# contactor_feedback.net
KiCad netlist of a schematic drawn in Altium Designer
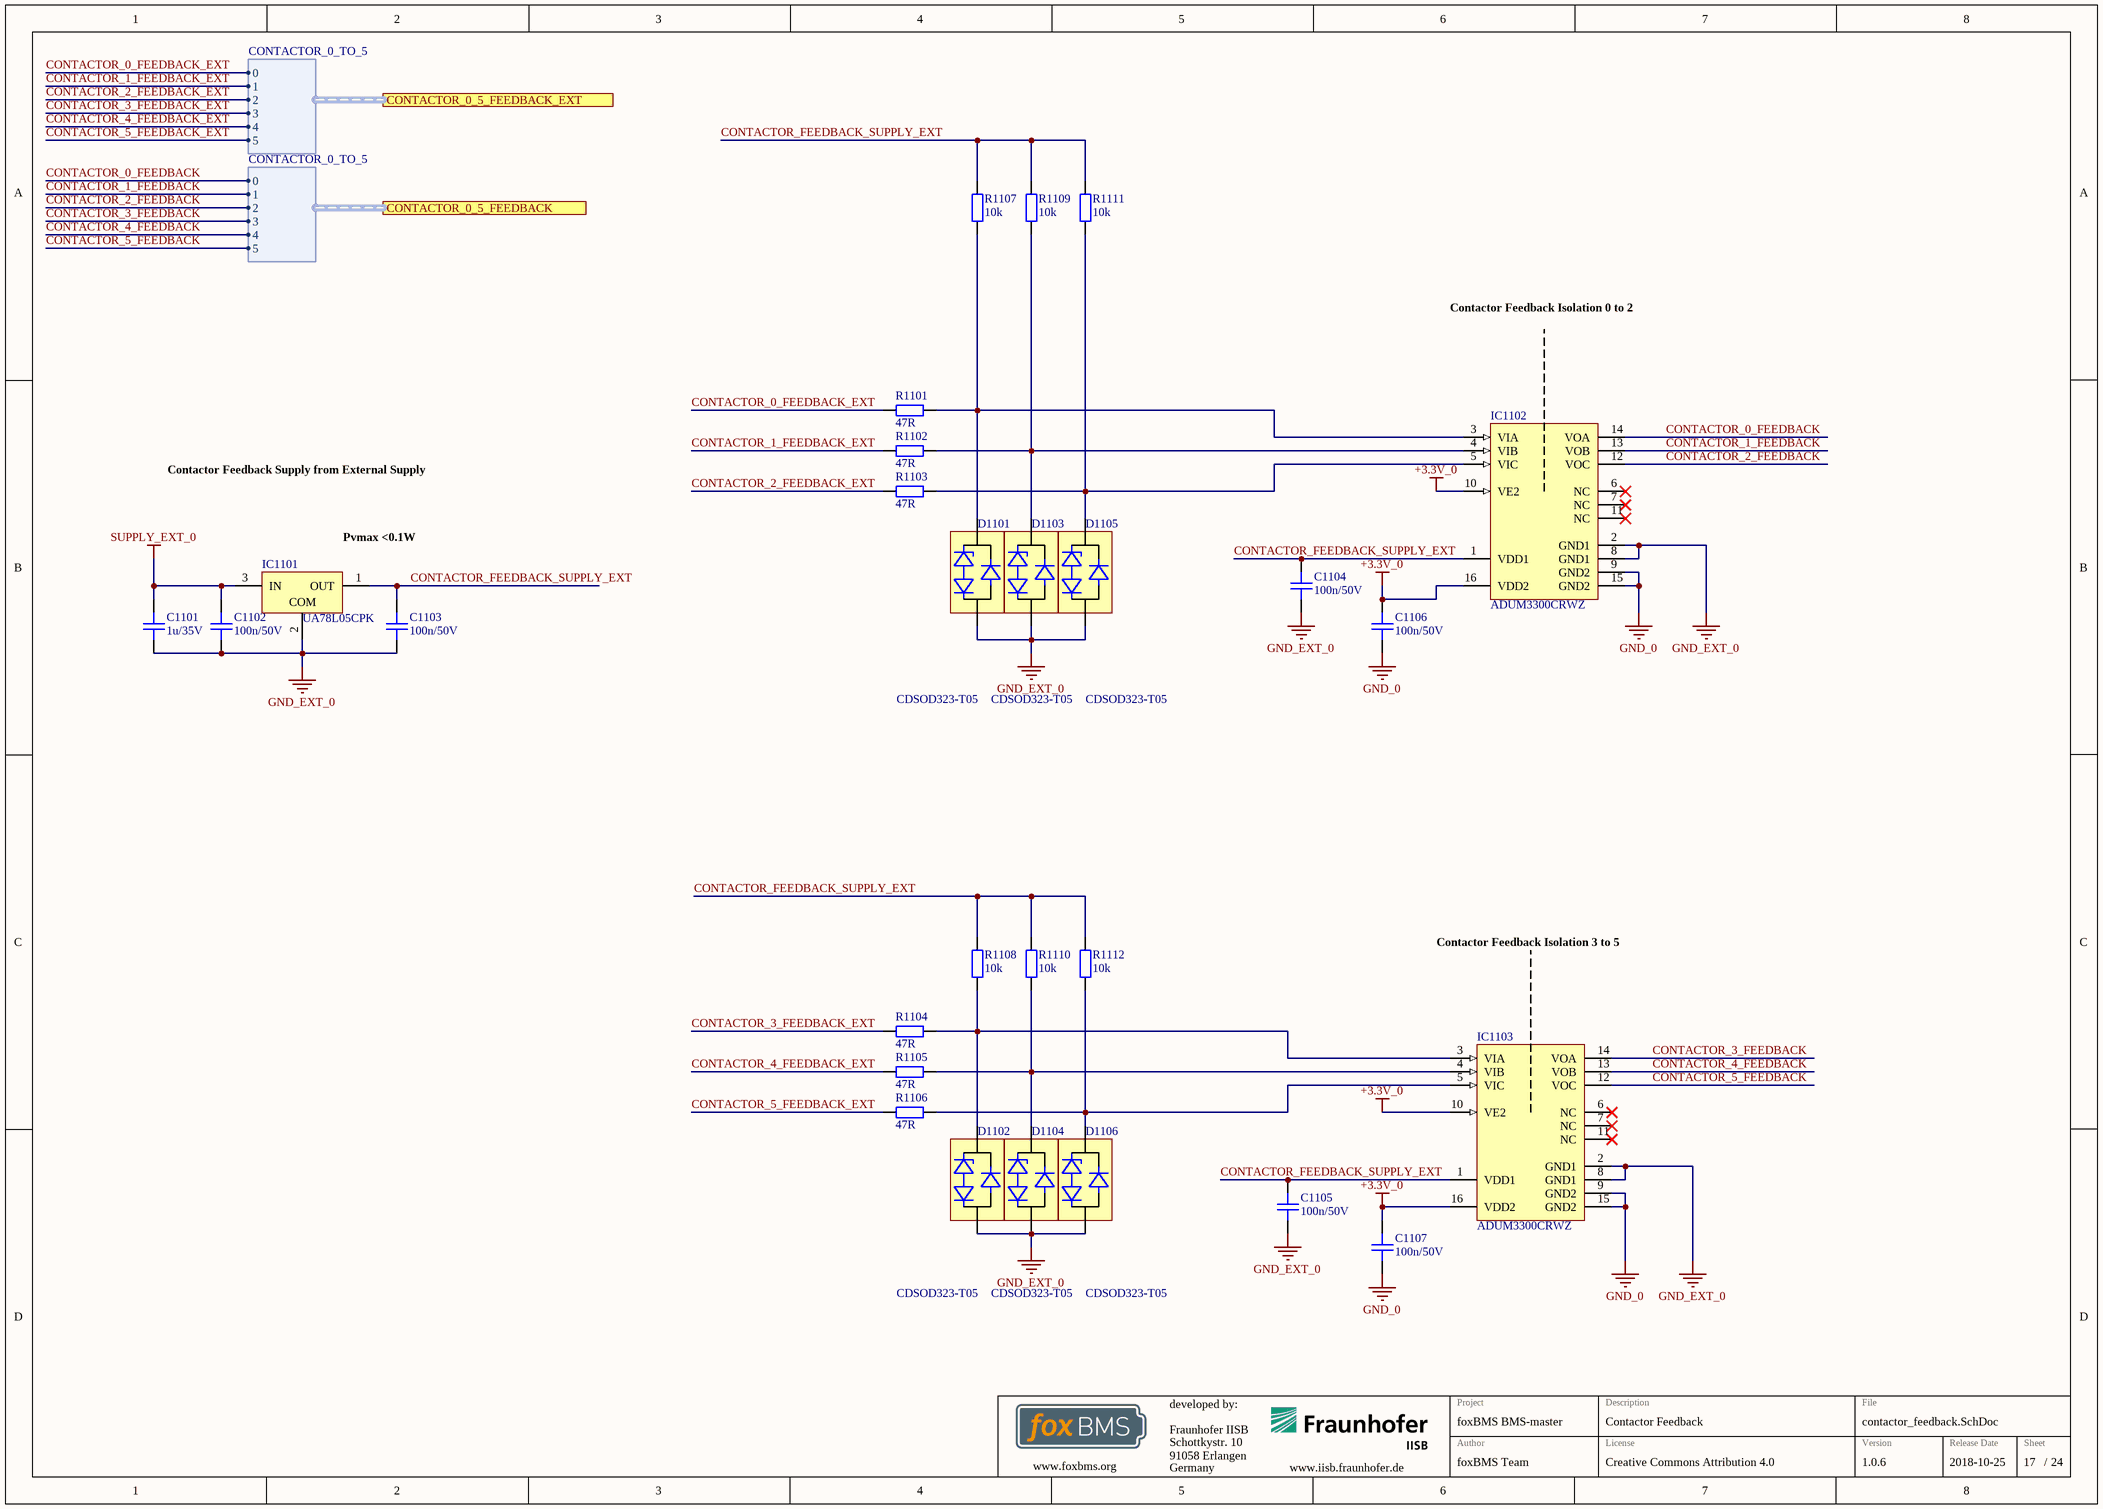
[diagram p0: contactor_feedback.SchDoc]

(export (version "E")
  (design (tool "Eeschema 10.0.6"))
  (components
    (comp (ref "C1101")
      (value "1u/35V")
      (footprint "CAPC1608X08N")
      (description "MLCC")
      (fields (field (name "PART NUMBER") "gen_C_ceramic_1u_35V_X7R_0603"))
      (libsource (lib "OE750") (part "C"))
    )
    (comp (ref "C1102")
      (value "100n/50V")
      (footprint "CAPC1608X08N")
      (description "MLCC")
      (fields (field (name "PART NUMBER") "gen_C_ceramic_100n_50V_X7R_0603"))
      (libsource (lib "OE750") (part "C"))
    )
    (comp (ref "C1103")
      (value "100n/50V")
      (footprint "CAPC1608X08N")
      (description "MLCC")
      (fields (field (name "PART NUMBER") "gen_C_ceramic_100n_50V_X7R_0603"))
      (libsource (lib "OE750") (part "C"))
    )
    (comp (ref "C1104")
      (value "100n/50V")
      (footprint "CAPC1608X08N")
      (description "MLCC")
      (fields (field (name "PART NUMBER") "gen_C_ceramic_100n_50V_X7R_0603"))
      (libsource (lib "OE750") (part "C"))
    )
    (comp (ref "C1105")
      (value "100n/50V")
      (footprint "CAPC1608X08N")
      (description "MLCC")
      (fields (field (name "PART NUMBER") "gen_C_ceramic_100n_50V_X7R_0603"))
      (libsource (lib "OE750") (part "C"))
    )
    (comp (ref "C1106")
      (value "100n/50V")
      (footprint "CAPC1608X08N")
      (description "MLCC")
      (fields (field (name "PART NUMBER") "gen_C_ceramic_100n_50V_X7R_0603"))
      (libsource (lib "OE750") (part "C"))
    )
    (comp (ref "C1107")
      (value "100n/50V")
      (footprint "CAPC1608X08N")
      (description "MLCC")
      (fields (field (name "PART NUMBER") "gen_C_ceramic_100n_50V_X7R_0603"))
      (libsource (lib "OE750") (part "C"))
    )
    (comp (ref "D1101")
      (value "CDSOD323-T05")
      (footprint "SODFL250X110-2N")
      (description "TVS Diode, CDSOD323 Series, Unidirectional, 5 V, 18.3 V, SOD-323, 2 Pins")
      (fields (field (name "MANUFACTURER") "Bourns"))
      (libsource (lib "OE750") (part "D_TVS_uni"))
    )
    (comp (ref "D1102")
      (value "CDSOD323-T05")
      (footprint "SODFL250X110-2N")
      (description "TVS Diode, CDSOD323 Series, Unidirectional, 5 V, 18.3 V, SOD-323, 2 Pins")
      (fields (field (name "MANUFACTURER") "Bourns"))
      (libsource (lib "OE750") (part "D_TVS_uni"))
    )
    (comp (ref "D1103")
      (value "CDSOD323-T05")
      (footprint "SODFL250X110-2N")
      (description "TVS Diode, CDSOD323 Series, Unidirectional, 5 V, 18.3 V, SOD-323, 2 Pins")
      (fields (field (name "MANUFACTURER") "Bourns"))
      (libsource (lib "OE750") (part "D_TVS_uni"))
    )
    (comp (ref "D1104")
      (value "CDSOD323-T05")
      (footprint "SODFL250X110-2N")
      (description "TVS Diode, CDSOD323 Series, Unidirectional, 5 V, 18.3 V, SOD-323, 2 Pins")
      (fields (field (name "MANUFACTURER") "Bourns"))
      (libsource (lib "OE750") (part "D_TVS_uni"))
    )
    (comp (ref "D1105")
      (value "CDSOD323-T05")
      (footprint "SODFL250X110-2N")
      (description "TVS Diode, CDSOD323 Series, Unidirectional, 5 V, 18.3 V, SOD-323, 2 Pins")
      (fields (field (name "MANUFACTURER") "Bourns"))
      (libsource (lib "OE750") (part "D_TVS_uni"))
    )
    (comp (ref "D1106")
      (value "CDSOD323-T05")
      (footprint "SODFL250X110-2N")
      (description "TVS Diode, CDSOD323 Series, Unidirectional, 5 V, 18.3 V, SOD-323, 2 Pins")
      (fields (field (name "MANUFACTURER") "Bourns"))
      (libsource (lib "OE750") (part "D_TVS_uni"))
    )
    (comp (ref "IC1101")
      (value "UA78L05CPK")
      (footprint "PK0003A_L")
      (fields (field (name "MANUFACTURER") "TexasInstruments"))
      (libsource (lib "Altium Content Vault") (part "TI-UA78L05-PK-3"))
    )
    (comp (ref "IC1102")
      (value "ADUM3300CRWZ")
      (footprint "ADI-RW-16_L")
      (fields (field (name "MANUFACTURER") "Analog Devices"))
      (libsource (lib "Altium Content Vault") (part "ADI-ADUMX300-RW-16"))
    )
    (comp (ref "IC1103")
      (value "ADUM3300CRWZ")
      (footprint "ADI-RW-16_L")
      (fields (field (name "MANUFACTURER") "Analog Devices"))
      (libsource (lib "Altium Content Vault") (part "ADI-ADUMX300-RW-16"))
    )
    (comp (ref "R1101")
      (value "47R")
      (footprint "RESC1608X05N")
      (description "SMD Resistor 47R 0603")
      (fields (field (name "PART NUMBER") "gen_R_47R_0603") (field (name "TOLERANCE") "1%"))
      (libsource (lib "OE750") (part "R"))
    )
    (comp (ref "R1102")
      (value "47R")
      (footprint "RESC1608X05N")
      (description "SMD Resistor 47R 0603")
      (fields (field (name "PART NUMBER") "gen_R_47R_0603") (field (name "TOLERANCE") "1%"))
      (libsource (lib "OE750") (part "R"))
    )
    (comp (ref "R1103")
      (value "47R")
      (footprint "RESC1608X05N")
      (description "SMD Resistor 47R 0603")
      (fields (field (name "PART NUMBER") "gen_R_47R_0603") (field (name "TOLERANCE") "1%"))
      (libsource (lib "OE750") (part "R"))
    )
    (comp (ref "R1104")
      (value "47R")
      (footprint "RESC1608X05N")
      (description "SMD Resistor 47R 0603")
      (fields (field (name "PART NUMBER") "gen_R_47R_0603") (field (name "TOLERANCE") "1%"))
      (libsource (lib "OE750") (part "R"))
    )
    (comp (ref "R1105")
      (value "47R")
      (footprint "RESC1608X05N")
      (description "SMD Resistor 47R 0603")
      (fields (field (name "PART NUMBER") "gen_R_47R_0603") (field (name "TOLERANCE") "1%"))
      (libsource (lib "OE750") (part "R"))
    )
    (comp (ref "R1106")
      (value "47R")
      (footprint "RESC1608X05N")
      (description "SMD Resistor 47R 0603")
      (fields (field (name "PART NUMBER") "gen_R_47R_0603") (field (name "TOLERANCE") "1%"))
      (libsource (lib "OE750") (part "R"))
    )
    (comp (ref "R1107")
      (value "10k")
      (footprint "RESC1608X05N")
      (description "SMD Resistor 10k 0603")
      (fields (field (name "PART NUMBER") "gen_R_10k_0603") (field (name "TOLERANCE") "1%"))
      (libsource (lib "OE750") (part "R"))
    )
    (comp (ref "R1108")
      (value "10k")
      (footprint "RESC1608X05N")
      (description "SMD Resistor 10k 0603")
      (fields (field (name "PART NUMBER") "gen_R_10k_0603") (field (name "TOLERANCE") "1%"))
      (libsource (lib "OE750") (part "R"))
    )
    (comp (ref "R1109")
      (value "10k")
      (footprint "RESC1608X05N")
      (description "SMD Resistor 10k 0603")
      (fields (field (name "PART NUMBER") "gen_R_10k_0603") (field (name "TOLERANCE") "1%"))
      (libsource (lib "OE750") (part "R"))
    )
    (comp (ref "R1110")
      (value "10k")
      (footprint "RESC1608X05N")
      (description "SMD Resistor 10k 0603")
      (fields (field (name "PART NUMBER") "gen_R_10k_0603") (field (name "TOLERANCE") "1%"))
      (libsource (lib "OE750") (part "R"))
    )
    (comp (ref "R1111")
      (value "10k")
      (footprint "RESC1608X05N")
      (description "SMD Resistor 10k 0603")
      (fields (field (name "PART NUMBER") "gen_R_10k_0603") (field (name "TOLERANCE") "1%"))
      (libsource (lib "OE750") (part "R"))
    )
    (comp (ref "R1112")
      (value "10k")
      (footprint "RESC1608X05N")
      (description "SMD Resistor 10k 0603")
      (fields (field (name "PART NUMBER") "gen_R_10k_0603") (field (name "TOLERANCE") "1%"))
      (libsource (lib "OE750") (part "R"))
    )
  )
  (nets
    (net (code "2") (name "+3.3V_0") (class "Default")
      (node (ref "C1106") (pin "1") (pinfunction "1_1") (pintype "passive"))
      (node (ref "C1107") (pin "1") (pinfunction "1_1") (pintype "passive"))
      (node (ref "IC1102") (pin "10") (pinfunction "VE2_10") (pintype "input"))
      (node (ref "IC1102") (pin "16") (pinfunction "VDD2_16") (pintype "power_in"))
      (node (ref "IC1103") (pin "10") (pinfunction "VE2_10") (pintype "input"))
      (node (ref "IC1103") (pin "16") (pinfunction "VDD2_16") (pintype "power_in"))
    )
    (net (code "3") (name "/CONTACTOR_0_FEEDBACK") (class "Default")
      (node (ref "IC1102") (pin "14") (pinfunction "VOA_14") (pintype "tri_state"))
    )
    (net (code "4") (name "/CONTACTOR_0_FEEDBACK_EXT") (class "Default")
      (node (ref "R1101") (pin "1") (pinfunction "1_1") (pintype "passive"))
    )
    (net (code "5") (name "/CONTACTOR_1_FEEDBACK") (class "Default")
      (node (ref "IC1102") (pin "13") (pinfunction "VOB_13") (pintype "tri_state"))
    )
    (net (code "6") (name "/CONTACTOR_1_FEEDBACK_EXT") (class "Default")
      (node (ref "R1102") (pin "1") (pinfunction "1_1") (pintype "passive"))
    )
    (net (code "7") (name "/CONTACTOR_2_FEEDBACK") (class "Default")
      (node (ref "IC1102") (pin "12") (pinfunction "VOC_12") (pintype "tri_state"))
    )
    (net (code "8") (name "/CONTACTOR_2_FEEDBACK_EXT") (class "Default")
      (node (ref "R1103") (pin "1") (pinfunction "1_1") (pintype "passive"))
    )
    (net (code "9") (name "/CONTACTOR_3_FEEDBACK") (class "Default")
      (node (ref "IC1103") (pin "14") (pinfunction "VOA_14") (pintype "tri_state"))
    )
    (net (code "10") (name "/CONTACTOR_3_FEEDBACK_EXT") (class "Default")
      (node (ref "R1104") (pin "2") (pinfunction "2_2") (pintype "passive"))
    )
    (net (code "11") (name "/CONTACTOR_4_FEEDBACK") (class "Default")
      (node (ref "IC1103") (pin "13") (pinfunction "VOB_13") (pintype "tri_state"))
    )
    (net (code "12") (name "/CONTACTOR_4_FEEDBACK_EXT") (class "Default")
      (node (ref "R1105") (pin "2") (pinfunction "2_2") (pintype "passive"))
    )
    (net (code "13") (name "/CONTACTOR_5_FEEDBACK") (class "Default")
      (node (ref "IC1103") (pin "12") (pinfunction "VOC_12") (pintype "tri_state"))
    )
    (net (code "14") (name "/CONTACTOR_5_FEEDBACK_EXT") (class "Default")
      (node (ref "R1106") (pin "2") (pinfunction "2_2") (pintype "passive"))
    )
    (net (code "15") (name "/CONTACTOR_FEEDBACK_SUPPLY_EXT") (class "Default")
      (node (ref "C1103") (pin "1") (pinfunction "1_1") (pintype "passive"))
      (node (ref "C1104") (pin "1") (pinfunction "1_1") (pintype "passive"))
      (node (ref "C1105") (pin "1") (pinfunction "1_1") (pintype "passive"))
      (node (ref "IC1101") (pin "1") (pinfunction "OUT_1") (pintype "power_in"))
      (node (ref "IC1102") (pin "1") (pinfunction "VDD1_1") (pintype "power_in"))
      (node (ref "IC1103") (pin "1") (pinfunction "VDD1_1") (pintype "power_in"))
      (node (ref "R1107") (pin "2") (pinfunction "2_2") (pintype "passive"))
      (node (ref "R1108") (pin "2") (pinfunction "2_2") (pintype "passive"))
      (node (ref "R1109") (pin "2") (pinfunction "2_2") (pintype "passive"))
      (node (ref "R1110") (pin "2") (pinfunction "2_2") (pintype "passive"))
      (node (ref "R1111") (pin "2") (pinfunction "2_2") (pintype "passive"))
      (node (ref "R1112") (pin "2") (pinfunction "2_2") (pintype "passive"))
    )
    (net (code "17") (name "GND_0") (class "Default")
      (node (ref "C1106") (pin "2") (pinfunction "2_2") (pintype "passive"))
      (node (ref "C1107") (pin "2") (pinfunction "2_2") (pintype "passive"))
      (node (ref "IC1102") (pin "15") (pinfunction "GND2_15") (pintype "power_in"))
      (node (ref "IC1102") (pin "9") (pinfunction "GND2_9") (pintype "power_in"))
      (node (ref "IC1103") (pin "15") (pinfunction "GND2_15") (pintype "power_in"))
      (node (ref "IC1103") (pin "9") (pinfunction "GND2_9") (pintype "power_in"))
    )
    (net (code "18") (name "GND_EXT_0") (class "Default")
      (node (ref "C1101") (pin "2") (pinfunction "2_2") (pintype "passive"))
      (node (ref "C1102") (pin "2") (pinfunction "2_2") (pintype "passive"))
      (node (ref "C1103") (pin "2") (pinfunction "2_2") (pintype "passive"))
      (node (ref "C1104") (pin "2") (pinfunction "2_2") (pintype "passive"))
      (node (ref "C1105") (pin "2") (pinfunction "2_2") (pintype "passive"))
      (node (ref "D1101") (pin "2") (pinfunction "A_2") (pintype "passive"))
      (node (ref "D1102") (pin "2") (pinfunction "A_2") (pintype "passive"))
      (node (ref "D1103") (pin "2") (pinfunction "A_2") (pintype "passive"))
      (node (ref "D1104") (pin "2") (pinfunction "A_2") (pintype "passive"))
      (node (ref "D1105") (pin "2") (pinfunction "A_2") (pintype "passive"))
      (node (ref "D1106") (pin "2") (pinfunction "A_2") (pintype "passive"))
      (node (ref "IC1101") (pin "2") (pinfunction "COM_2") (pintype "power_in"))
      (node (ref "IC1102") (pin "2") (pinfunction "GND1_2") (pintype "power_in"))
      (node (ref "IC1102") (pin "8") (pinfunction "GND1_8") (pintype "power_in"))
      (node (ref "IC1103") (pin "2") (pinfunction "GND1_2") (pintype "power_in"))
      (node (ref "IC1103") (pin "8") (pinfunction "GND1_8") (pintype "power_in"))
    )
    (net (code "19") (name "Net-(D1101-K)") (class "Default")
      (node (ref "D1101") (pin "1") (pinfunction "K_1") (pintype "passive"))
      (node (ref "IC1102") (pin "3") (pinfunction "VIA_3") (pintype "input"))
      (node (ref "R1101") (pin "2") (pinfunction "2_2") (pintype "passive"))
      (node (ref "R1107") (pin "1") (pinfunction "1_1") (pintype "passive"))
    )
    (net (code "20") (name "Net-(D1102-K)") (class "Default")
      (node (ref "D1102") (pin "1") (pinfunction "K_1") (pintype "passive"))
      (node (ref "IC1103") (pin "3") (pinfunction "VIA_3") (pintype "input"))
      (node (ref "R1104") (pin "1") (pinfunction "1_1") (pintype "passive"))
      (node (ref "R1108") (pin "1") (pinfunction "1_1") (pintype "passive"))
    )
    (net (code "21") (name "Net-(D1103-K)") (class "Default")
      (node (ref "D1103") (pin "1") (pinfunction "K_1") (pintype "passive"))
      (node (ref "IC1102") (pin "4") (pinfunction "VIB_4") (pintype "input"))
      (node (ref "R1102") (pin "2") (pinfunction "2_2") (pintype "passive"))
      (node (ref "R1109") (pin "1") (pinfunction "1_1") (pintype "passive"))
    )
    (net (code "22") (name "Net-(D1104-K)") (class "Default")
      (node (ref "D1104") (pin "1") (pinfunction "K_1") (pintype "passive"))
      (node (ref "IC1103") (pin "4") (pinfunction "VIB_4") (pintype "input"))
      (node (ref "R1105") (pin "1") (pinfunction "1_1") (pintype "passive"))
      (node (ref "R1110") (pin "1") (pinfunction "1_1") (pintype "passive"))
    )
    (net (code "23") (name "Net-(D1105-K)") (class "Default")
      (node (ref "D1105") (pin "1") (pinfunction "K_1") (pintype "passive"))
      (node (ref "IC1102") (pin "5") (pinfunction "VIC_5") (pintype "input"))
      (node (ref "R1103") (pin "2") (pinfunction "2_2") (pintype "passive"))
      (node (ref "R1111") (pin "1") (pinfunction "1_1") (pintype "passive"))
    )
    (net (code "24") (name "Net-(D1106-K)") (class "Default")
      (node (ref "D1106") (pin "1") (pinfunction "K_1") (pintype "passive"))
      (node (ref "IC1103") (pin "5") (pinfunction "VIC_5") (pintype "input"))
      (node (ref "R1106") (pin "1") (pinfunction "1_1") (pintype "passive"))
      (node (ref "R1112") (pin "1") (pinfunction "1_1") (pintype "passive"))
    )
    (net (code "25") (name "SUPPLY_EXT_0") (class "Default")
      (node (ref "C1101") (pin "1") (pinfunction "1_1") (pintype "passive"))
      (node (ref "C1102") (pin "1") (pinfunction "1_1") (pintype "passive"))
      (node (ref "IC1101") (pin "3") (pinfunction "IN_3") (pintype "power_in"))
    )
    (net (code "26") (name "unconnected-(IC1102-NC-Pad6)") (class "Default")
      (node (ref "IC1102") (pin "6") (pinfunction "NC_6") (pintype "passive+no_connect"))
    )
    (net (code "27") (name "unconnected-(IC1102-NC-Pad7)") (class "Default")
      (node (ref "IC1102") (pin "7") (pinfunction "NC_7") (pintype "passive+no_connect"))
    )
    (net (code "28") (name "unconnected-(IC1102-NC-Pad11)") (class "Default")
      (node (ref "IC1102") (pin "11") (pinfunction "NC_11") (pintype "passive+no_connect"))
    )
    (net (code "29") (name "unconnected-(IC1103-NC-Pad6)") (class "Default")
      (node (ref "IC1103") (pin "6") (pinfunction "NC_6") (pintype "passive+no_connect"))
    )
    (net (code "30") (name "unconnected-(IC1103-NC-Pad7)") (class "Default")
      (node (ref "IC1103") (pin "7") (pinfunction "NC_7") (pintype "passive+no_connect"))
    )
    (net (code "31") (name "unconnected-(IC1103-NC-Pad11)") (class "Default")
      (node (ref "IC1103") (pin "11") (pinfunction "NC_11") (pintype "passive+no_connect"))
    )
  )
)
